# Schematic.net
KiCad netlist of a schematic drawn in Altium Designer
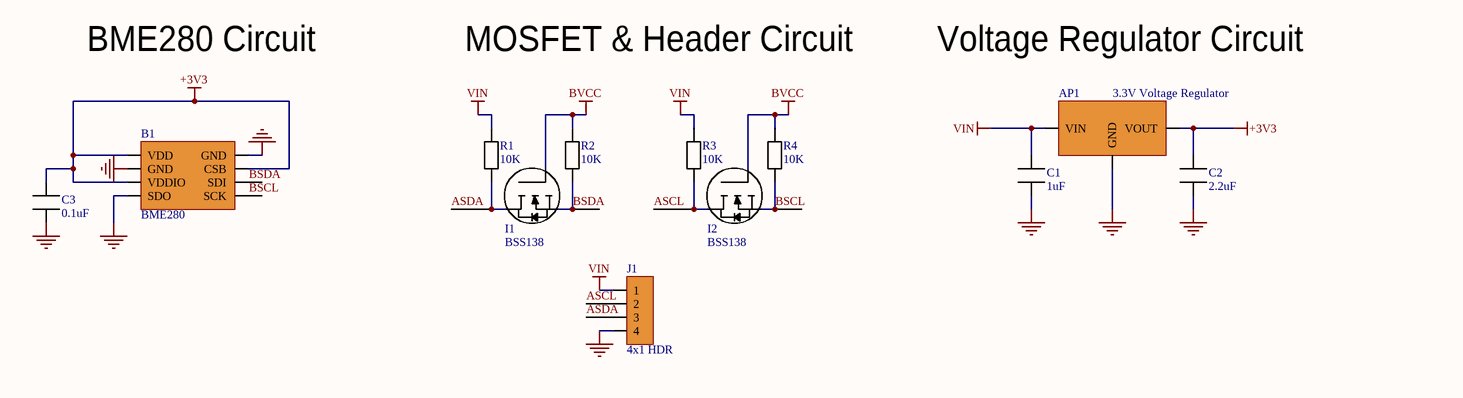
[diagram p0: Schematic.SchDoc]

(export (version "E")
  (design (tool "Eeschema 10.0.6"))
  (components
    (comp (ref "AP1")
      (value "3.3V Voltage Regulator")
      (footprint "Voltage Regulator")
      (description "IC REG LINEAR 3.3V 150MA SOT89")
      (fields
        (field (name "MANUFACTURER") "Diodes")
        (field (name "MANUFACTURER PART NUMBER") "AP7381-33Y-13")
      )
      (libsource (lib "Schematic Library") (part "AP7381-33Y-13"))
    )
    (comp (ref "B1")
      (value "BME280")
      (footprint "BME280")
      (description "Pressure, Temperature and Humidity Sensor Digital Output 1.8V 8-Pin LGA T/R")
      (fields (field (name "MANUFACTURER") "Bosch"))
      (libsource (lib "Schematic Library") (part "BME280"))
    )
    (comp (ref "C1")
      (value "1uF")
      (footprint "0.1uF Capcaitor")
      (description "LMK105BJ105KV-F")
      (fields (field (name "MANUFACTURER") "Taiyo Yuden") (field (name "TOLERANCE") "10%"))
      (libsource (lib "Schematic Library") (part "LMK105BJ105KV-F"))
    )
    (comp (ref "C2")
      (value "2.2uF")
      (footprint "22uF Capacitor")
      (description "TAIYO YUDEN         LMK105BJ225MV-F            CERAMIC CAPACITOR, 2.2UF, 10V, X5R, 20%, 0402")
      (fields
        (field (name "MANUFACTURER") "Taiyo Yuden")
        (field (name "MANUFACTURER PART NUMBER") "LMK105BJ225MV-F")
      )
      (libsource (lib "Schematic Library") (part "LMK105BJ225MV-F"))
    )
    (comp (ref "C3")
      (value "0.1uF")
      (footprint "0.1uF Capcaitor")
      (description "TAIYO YUDEN - EMK105BJ104KV-F - CERAMIC CAPACITOR, 0.1UF, 16V, X5R, 10%, 0402, FULL REEL")
      (fields
        (field (name "MANUFACTURER") "Taiyo Yuden")
        (field (name "MANUFACTURER PART NUMBER") "EMK105BJ104KV-F")
      )
      (libsource (lib "Schematic Library") (part "EMK105BJ104KV-F"))
    )
    (comp (ref "I1")
      (value "BSS138")
      (footprint "MOSFET")
      (description "Trans MOSFET N-CH 50V 0.22A 3-Pin SOT-23 T/R")
      (fields (field (name "MANUFACTURER") "ON Semiconductor / Fairchild"))
      (libsource (lib "Schematic Library") (part "BSS138"))
    )
    (comp (ref "I2")
      (value "BSS138")
      (footprint "MOSFET")
      (description "Trans MOSFET N-CH 50V 0.22A 3-Pin SOT-23 T/R")
      (fields (field (name "MANUFACTURER") "ON Semiconductor / Fairchild"))
      (libsource (lib "Schematic Library") (part "BSS138"))
    )
    (comp (ref "J1")
      (value "4x1 HDR")
      (footprint "Header 4x1")
      (description "CONN HEADER VERT 4POS 2.54MM")
      (fields
        (field (name "MANUFACTURER") "Wurth Electronics")
        (field (name "MANUFACTURER PART NUMBER") "61300411121")
      )
      (libsource (lib "Schematic Library") (part "61300411121"))
    )
    (comp (ref "R1")
      (value "10K")
      (footprint "10K Resistor")
      (description "RES 10K OHM 1% 1/16W 0402")
      (fields
        (field (name "MANUFACTURER") "Stackpole Electronics")
        (field (name "MANUFACTURER PART NUMBER") "RMCF0402FT10K0")
      )
      (libsource (lib "Schematic Library") (part "RMCF0402FT10K0"))
    )
    (comp (ref "R2")
      (value "10K")
      (footprint "10K Resistor")
      (description "RES 10K OHM 1% 1/16W 0402")
      (fields
        (field (name "MANUFACTURER") "Stackpole Electronics")
        (field (name "MANUFACTURER PART NUMBER") "RMCF0402FT10K0")
      )
      (libsource (lib "Schematic Library") (part "RMCF0402FT10K0"))
    )
    (comp (ref "R3")
      (value "10K")
      (footprint "10K Resistor")
      (description "RES 10K OHM 1% 1/16W 0402")
      (fields
        (field (name "MANUFACTURER") "Stackpole Electronics")
        (field (name "MANUFACTURER PART NUMBER") "RMCF0402FT10K0")
      )
      (libsource (lib "Schematic Library") (part "RMCF0402FT10K0"))
    )
    (comp (ref "R4")
      (value "10K")
      (footprint "10K Resistor")
      (description "RES 10K OHM 1% 1/16W 0402")
      (fields
        (field (name "MANUFACTURER") "Stackpole Electronics")
        (field (name "MANUFACTURER PART NUMBER") "RMCF0402FT10K0")
      )
      (libsource (lib "Schematic Library") (part "RMCF0402FT10K0"))
    )
  )
  (nets
    (net (code "1") (name "+3V3") (class "Default")
      (node (ref "AP1") (pin "1") (pinfunction "VOUT_1") (pintype "passive"))
      (node (ref "B1") (pin "2") (pinfunction "CSB_2") (pintype "passive"))
      (node (ref "B1") (pin "6") (pinfunction "VDDIO_6") (pintype "passive"))
      (node (ref "B1") (pin "8") (pinfunction "VDD_8") (pintype "passive"))
      (node (ref "C2") (pin "2") (pinfunction "2_2") (pintype "passive"))
      (node (ref "C3") (pin "2") (pinfunction "2_2") (pintype "passive"))
    )
    (net (code "2") (name "/ASCL") (class "Default")
      (node (ref "I2") (pin "2") (pinfunction "2_2") (pintype "passive"))
      (node (ref "J1") (pin "2") (pinfunction "2_2") (pintype "passive"))
      (node (ref "R3") (pin "1") (pinfunction "1_1") (pintype "passive"))
    )
    (net (code "3") (name "/ASDA") (class "Default")
      (node (ref "I1") (pin "2") (pinfunction "2_2") (pintype "passive"))
      (node (ref "J1") (pin "3") (pinfunction "3_3") (pintype "passive"))
      (node (ref "R1") (pin "1") (pinfunction "1_1") (pintype "passive"))
    )
    (net (code "4") (name "/BSCL") (class "Default")
      (node (ref "B1") (pin "4") (pinfunction "SCK_4") (pintype "passive"))
      (node (ref "I2") (pin "3") (pinfunction "3_3") (pintype "passive"))
      (node (ref "R4") (pin "1") (pinfunction "1_1") (pintype "passive"))
    )
    (net (code "5") (name "/BSDA") (class "Default")
      (node (ref "B1") (pin "3") (pinfunction "SDI_3") (pintype "passive"))
      (node (ref "I1") (pin "3") (pinfunction "3_3") (pintype "passive"))
      (node (ref "R2") (pin "1") (pinfunction "1_1") (pintype "passive"))
    )
    (net (code "6") (name "BVCC") (class "Default")
      (node (ref "I1") (pin "1") (pinfunction "1_1") (pintype "passive"))
      (node (ref "I2") (pin "1") (pinfunction "1_1") (pintype "passive"))
      (node (ref "R2") (pin "2") (pinfunction "2_2") (pintype "passive"))
      (node (ref "R4") (pin "2") (pinfunction "2_2") (pintype "passive"))
    )
    (net (code "7") (name "GND") (class "Default")
      (node (ref "AP1") (pin "2") (pinfunction "GND_2") (pintype "passive"))
      (node (ref "B1") (pin "1") (pinfunction "GND_1") (pintype "passive"))
      (node (ref "B1") (pin "5") (pinfunction "SDO_5") (pintype "passive"))
      (node (ref "B1") (pin "7") (pinfunction "GND_7") (pintype "passive"))
      (node (ref "C1") (pin "1") (pinfunction "1_1") (pintype "passive"))
      (node (ref "C2") (pin "1") (pinfunction "1_1") (pintype "passive"))
      (node (ref "C3") (pin "1") (pinfunction "1_1") (pintype "passive"))
      (node (ref "J1") (pin "4") (pinfunction "4_4") (pintype "passive"))
    )
    (net (code "8") (name "VIN") (class "Default")
      (node (ref "AP1") (pin "3") (pinfunction "VIN_3") (pintype "passive"))
      (node (ref "C1") (pin "2") (pinfunction "2_2") (pintype "passive"))
      (node (ref "J1") (pin "1") (pinfunction "1_1") (pintype "passive"))
      (node (ref "R1") (pin "2") (pinfunction "2_2") (pintype "passive"))
      (node (ref "R3") (pin "2") (pinfunction "2_2") (pintype "passive"))
    )
  )
)
